# sensorPlate.net
KiCad netlist of a schematic drawn in Altium Designer
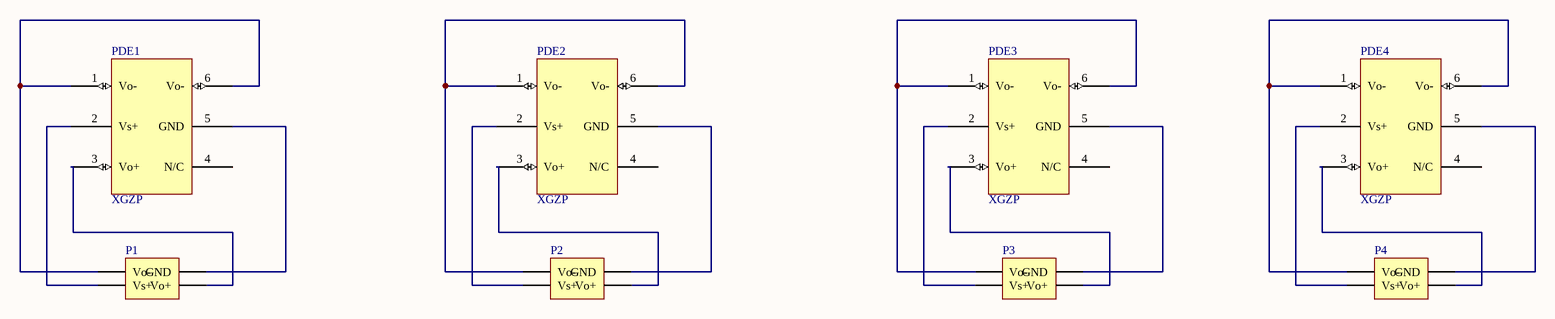
[diagram p0: sensorPlate.SchDoc]

(export (version "E")
  (design (tool "Eeschema 10.0.6"))
  (components
    (comp (ref "P1")
      (value "Header 2X2")
      (footprint "HDR2X2")
      (description "Header, 2-Pin, Dual row")
      (fields (field (name "PUBLISHER") "Altium Limited"))
      (libsource (lib "Miscellaneous Connectors") (part "Header 2X2"))
    )
    (comp (ref "P2")
      (value "Header 2X2")
      (footprint "HDR2X2")
      (description "Header, 2-Pin, Dual row")
      (fields (field (name "PUBLISHER") "Altium Limited"))
      (libsource (lib "Miscellaneous Connectors") (part "Header 2X2"))
    )
    (comp (ref "P3")
      (value "Header 2X2")
      (footprint "HDR2X2")
      (description "Header, 2-Pin, Dual row")
      (fields (field (name "PUBLISHER") "Altium Limited"))
      (libsource (lib "Miscellaneous Connectors") (part "Header 2X2"))
    )
    (comp (ref "P4")
      (value "Header 2X2")
      (footprint "HDR2X2")
      (description "Header, 2-Pin, Dual row")
      (fields (field (name "PUBLISHER") "Altium Limited"))
      (libsource (lib "Miscellaneous Connectors") (part "Header 2X2"))
    )
    (comp (ref "PDE1") (value "XGZP") (footprint "XGZP_Footprint") (libsource (lib "Lib") (part "XGZP")))
    (comp (ref "PDE2") (value "XGZP") (footprint "XGZP_Footprint") (libsource (lib "Lib") (part "XGZP")))
    (comp (ref "PDE3") (value "XGZP") (footprint "XGZP_Footprint") (libsource (lib "Lib") (part "XGZP")))
    (comp (ref "PDE4") (value "XGZP") (footprint "XGZP_Footprint") (libsource (lib "Lib") (part "XGZP")))
  )
  (nets
    (net (code "1") (name "Net-(P1-GND)") (class "Default")
      (node (ref "P1") (pin "3") (pinfunction "GND_3") (pintype "passive"))
      (node (ref "PDE1") (pin "5") (pinfunction "GND_5") (pintype "power_in"))
    )
    (net (code "2") (name "Net-(P1-Vo+)") (class "Default")
      (node (ref "P1") (pin "1") (pinfunction "Vo+_1") (pintype "passive"))
      (node (ref "PDE1") (pin "3") (pinfunction "Vo+_3") (pintype "bidirectional"))
    )
    (net (code "3") (name "Net-(P1-Vo-)") (class "Default")
      (node (ref "P1") (pin "4") (pinfunction "Vo-_4") (pintype "passive"))
      (node (ref "PDE1") (pin "1") (pinfunction "Vo-_1") (pintype "bidirectional"))
      (node (ref "PDE1") (pin "6") (pinfunction "Vo-_6") (pintype "bidirectional"))
    )
    (net (code "4") (name "Net-(P1-Vs+)") (class "Default")
      (node (ref "P1") (pin "2") (pinfunction "Vs+_2") (pintype "passive"))
      (node (ref "PDE1") (pin "2") (pinfunction "Vs+_2") (pintype "power_in"))
    )
    (net (code "5") (name "Net-(P2-GND)") (class "Default")
      (node (ref "P2") (pin "3") (pinfunction "GND_3") (pintype "passive"))
      (node (ref "PDE2") (pin "5") (pinfunction "GND_5") (pintype "power_in"))
    )
    (net (code "6") (name "Net-(P2-Vo+)") (class "Default")
      (node (ref "P2") (pin "1") (pinfunction "Vo+_1") (pintype "passive"))
      (node (ref "PDE2") (pin "3") (pinfunction "Vo+_3") (pintype "bidirectional"))
    )
    (net (code "7") (name "Net-(P2-Vo-)") (class "Default")
      (node (ref "P2") (pin "4") (pinfunction "Vo-_4") (pintype "passive"))
      (node (ref "PDE2") (pin "1") (pinfunction "Vo-_1") (pintype "bidirectional"))
      (node (ref "PDE2") (pin "6") (pinfunction "Vo-_6") (pintype "bidirectional"))
    )
    (net (code "8") (name "Net-(P2-Vs+)") (class "Default")
      (node (ref "P2") (pin "2") (pinfunction "Vs+_2") (pintype "passive"))
      (node (ref "PDE2") (pin "2") (pinfunction "Vs+_2") (pintype "power_in"))
    )
    (net (code "9") (name "Net-(P3-GND)") (class "Default")
      (node (ref "P3") (pin "3") (pinfunction "GND_3") (pintype "passive"))
      (node (ref "PDE3") (pin "5") (pinfunction "GND_5") (pintype "power_in"))
    )
    (net (code "10") (name "Net-(P3-Vo+)") (class "Default")
      (node (ref "P3") (pin "1") (pinfunction "Vo+_1") (pintype "passive"))
      (node (ref "PDE3") (pin "3") (pinfunction "Vo+_3") (pintype "bidirectional"))
    )
    (net (code "11") (name "Net-(P3-Vo-)") (class "Default")
      (node (ref "P3") (pin "4") (pinfunction "Vo-_4") (pintype "passive"))
      (node (ref "PDE3") (pin "1") (pinfunction "Vo-_1") (pintype "bidirectional"))
      (node (ref "PDE3") (pin "6") (pinfunction "Vo-_6") (pintype "bidirectional"))
    )
    (net (code "12") (name "Net-(P3-Vs+)") (class "Default")
      (node (ref "P3") (pin "2") (pinfunction "Vs+_2") (pintype "passive"))
      (node (ref "PDE3") (pin "2") (pinfunction "Vs+_2") (pintype "power_in"))
    )
    (net (code "13") (name "Net-(P4-GND)") (class "Default")
      (node (ref "P4") (pin "3") (pinfunction "GND_3") (pintype "passive"))
      (node (ref "PDE4") (pin "5") (pinfunction "GND_5") (pintype "power_in"))
    )
    (net (code "14") (name "Net-(P4-Vo+)") (class "Default")
      (node (ref "P4") (pin "1") (pinfunction "Vo+_1") (pintype "passive"))
      (node (ref "PDE4") (pin "3") (pinfunction "Vo+_3") (pintype "bidirectional"))
    )
    (net (code "15") (name "Net-(P4-Vo-)") (class "Default")
      (node (ref "P4") (pin "4") (pinfunction "Vo-_4") (pintype "passive"))
      (node (ref "PDE4") (pin "1") (pinfunction "Vo-_1") (pintype "bidirectional"))
      (node (ref "PDE4") (pin "6") (pinfunction "Vo-_6") (pintype "bidirectional"))
    )
    (net (code "16") (name "Net-(P4-Vs+)") (class "Default")
      (node (ref "P4") (pin "2") (pinfunction "Vs+_2") (pintype "passive"))
      (node (ref "PDE4") (pin "2") (pinfunction "Vs+_2") (pintype "power_in"))
    )
    (net (code "17") (name "unconnected-(PDE1-N{slash}C-Pad4)") (class "Default")
      (node (ref "PDE1") (pin "4") (pinfunction "N/C_4") (pintype "passive"))
    )
    (net (code "18") (name "unconnected-(PDE2-N{slash}C-Pad4)") (class "Default")
      (node (ref "PDE2") (pin "4") (pinfunction "N/C_4") (pintype "passive"))
    )
    (net (code "19") (name "unconnected-(PDE3-N{slash}C-Pad4)") (class "Default")
      (node (ref "PDE3") (pin "4") (pinfunction "N/C_4") (pintype "passive"))
    )
    (net (code "20") (name "unconnected-(PDE4-N{slash}C-Pad4)") (class "Default")
      (node (ref "PDE4") (pin "4") (pinfunction "N/C_4") (pintype "passive"))
    )
  )
)
